# v1_2_0.net
KiCad netlist of a schematic drawn in EAGLE
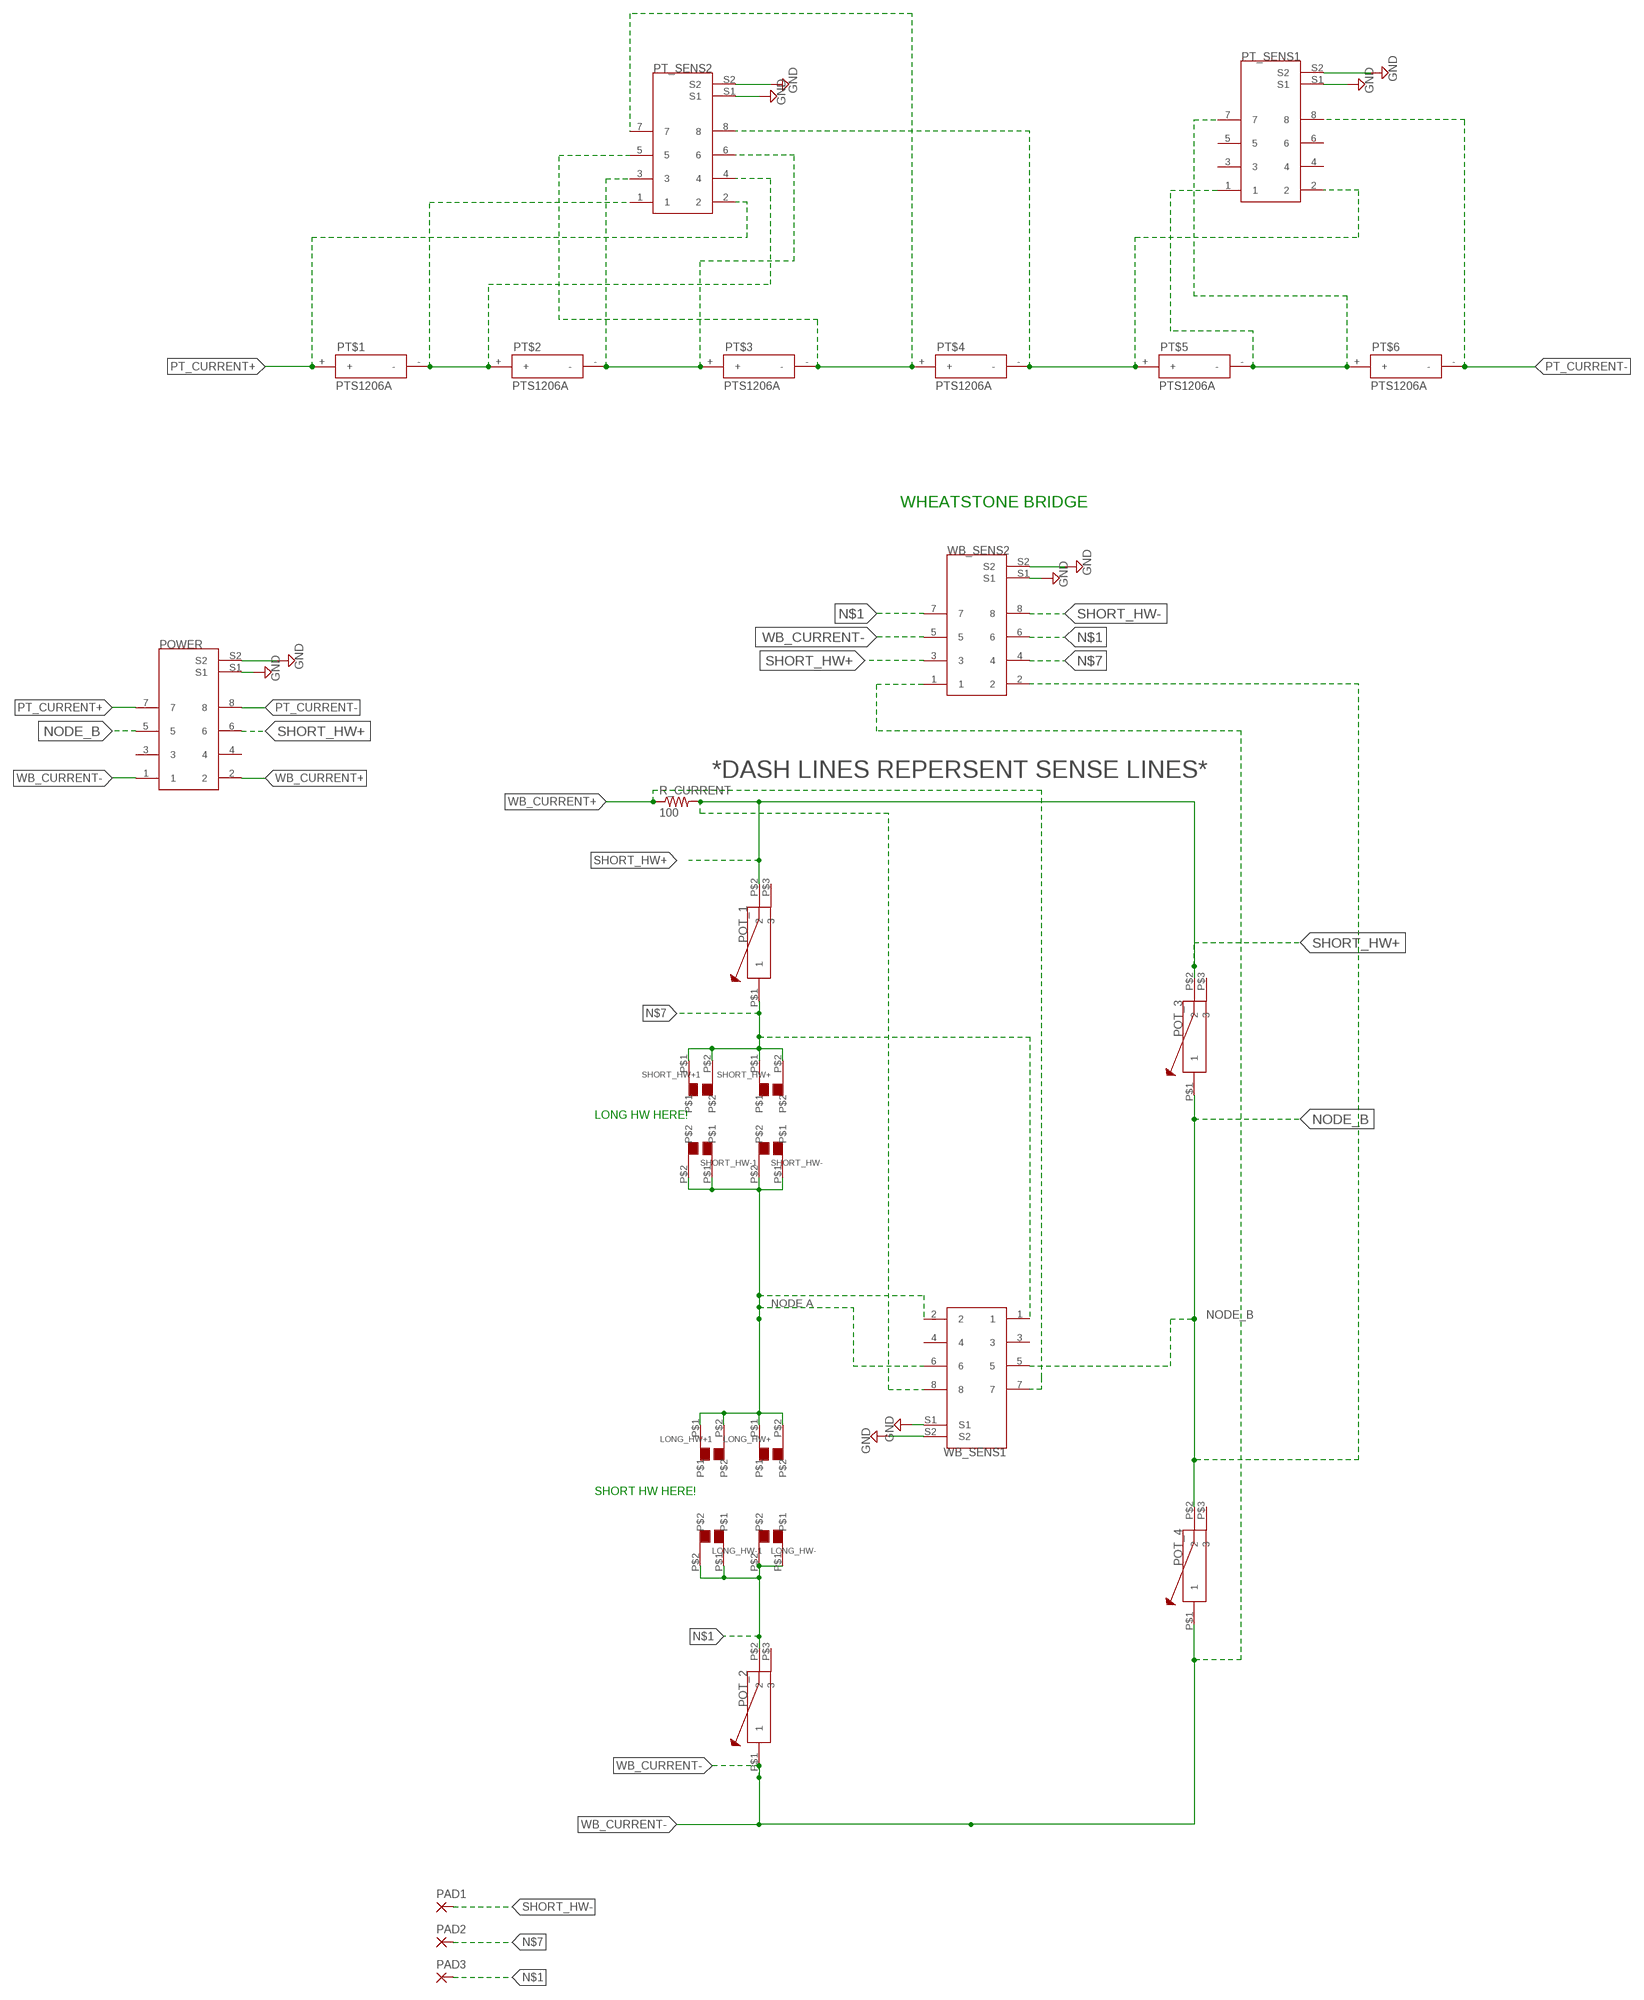
[diagram p0: schematic, sheet 1]

(export (version "E")
  (design (tool "Eeschema 10.0.6"))
  (components
    (comp (ref "LONG_HW+")
      (value "WIREPOINT_1A")
      (footprint "eagle-import:WIREPOINT")
      (libsource (lib "eagle-import") (part "WIREPOINT_1A"))
    )
    (comp (ref "LONG_HW+1")
      (value "WIREPOINT_1A")
      (footprint "eagle-import:WIREPOINT")
      (libsource (lib "eagle-import") (part "WIREPOINT_1A"))
    )
    (comp (ref "LONG_HW-")
      (value "WIREPOINT_1A")
      (footprint "eagle-import:WIREPOINT")
      (libsource (lib "eagle-import") (part "WIREPOINT_1A"))
    )
    (comp (ref "LONG_HW-1")
      (value "WIREPOINT_1A")
      (footprint "eagle-import:WIREPOINT")
      (libsource (lib "eagle-import") (part "WIREPOINT_1A"))
    )
    (comp (ref "PAD1")
      (value "2,15/1,0")
      (footprint "eagle-import:2,15_1,0")
      (libsource (lib "eagle-import") (part "2,15/1,0"))
    )
    (comp (ref "PAD2")
      (value "2,15/1,0")
      (footprint "eagle-import:2,15_1,0")
      (libsource (lib "eagle-import") (part "2,15/1,0"))
    )
    (comp (ref "PAD3")
      (value "2,15/1,0")
      (footprint "eagle-import:2,15_1,0")
      (libsource (lib "eagle-import") (part "2,15/1,0"))
    )
    (comp (ref "POT_1")
      (value "67WR200LFR$1")
      (footprint "eagle-import:67WR200LF")
      (libsource (lib "eagle-import") (part "67WR200LFR$1"))
    )
    (comp (ref "POT_2")
      (value "67WR200LFR$1")
      (footprint "eagle-import:67WR200LF")
      (libsource (lib "eagle-import") (part "67WR200LFR$1"))
    )
    (comp (ref "POT_3")
      (value "67WR200LFR$1")
      (footprint "eagle-import:67WR200LF")
      (libsource (lib "eagle-import") (part "67WR200LFR$1"))
    )
    (comp (ref "POT_4")
      (value "67WR200LFR$1")
      (footprint "eagle-import:67WR200LF")
      (libsource (lib "eagle-import") (part "67WR200LFR$1"))
    )
    (comp (ref "POWER")
      (value "RJ45_CONNECTOR")
      (footprint "eagle-import:RJ45_CONNNECTOR")
      (libsource (lib "eagle-import") (part "RJ45_CONNECTOR"))
    )
    (comp (ref "PT$1")
      (value "PTS1206A")
      (footprint "eagle-import:CAPMP3216X166")
      (libsource (lib "eagle-import") (part "PTS1206A"))
    )
    (comp (ref "PT$2")
      (value "PTS1206A")
      (footprint "eagle-import:CAPMP3216X166")
      (libsource (lib "eagle-import") (part "PTS1206A"))
    )
    (comp (ref "PT$3")
      (value "PTS1206A")
      (footprint "eagle-import:CAPMP3216X166")
      (libsource (lib "eagle-import") (part "PTS1206A"))
    )
    (comp (ref "PT$4")
      (value "PTS1206A")
      (footprint "eagle-import:CAPMP3216X166")
      (libsource (lib "eagle-import") (part "PTS1206A"))
    )
    (comp (ref "PT$5")
      (value "PTS1206A")
      (footprint "eagle-import:CAPMP3216X166")
      (libsource (lib "eagle-import") (part "PTS1206A"))
    )
    (comp (ref "PT$6")
      (value "PTS1206A")
      (footprint "eagle-import:CAPMP3216X166")
      (libsource (lib "eagle-import") (part "PTS1206A"))
    )
    (comp (ref "PT_SENS1")
      (value "RJ45_CONNECTOR")
      (footprint "eagle-import:RJ45_CONNNECTOR")
      (libsource (lib "eagle-import") (part "RJ45_CONNECTOR"))
    )
    (comp (ref "PT_SENS2")
      (value "RJ45_CONNECTOR")
      (footprint "eagle-import:RJ45_CONNNECTOR")
      (libsource (lib "eagle-import") (part "RJ45_CONNECTOR"))
    )
    (comp (ref "R_CURRENT")
      (value "100")
      (footprint "eagle-import:M0805")
      (libsource (lib "eagle-import") (part "R-US_M0805"))
    )
    (comp (ref "SHORT_HW+")
      (value "WIREPOINT_1A")
      (footprint "eagle-import:WIREPOINT")
      (libsource (lib "eagle-import") (part "WIREPOINT_1A"))
    )
    (comp (ref "SHORT_HW+1")
      (value "WIREPOINT_1A")
      (footprint "eagle-import:WIREPOINT")
      (libsource (lib "eagle-import") (part "WIREPOINT_1A"))
    )
    (comp (ref "SHORT_HW-")
      (value "WIREPOINT_1A")
      (footprint "eagle-import:WIREPOINT")
      (libsource (lib "eagle-import") (part "WIREPOINT_1A"))
    )
    (comp (ref "SHORT_HW-1")
      (value "WIREPOINT_1A")
      (footprint "eagle-import:WIREPOINT")
      (libsource (lib "eagle-import") (part "WIREPOINT_1A"))
    )
    (comp (ref "WB_SENS1")
      (value "RJ45_CONNECTOR")
      (footprint "eagle-import:RJ45_CONNNECTOR")
      (libsource (lib "eagle-import") (part "RJ45_CONNECTOR"))
    )
    (comp (ref "WB_SENS2")
      (value "RJ45_CONNECTOR")
      (footprint "eagle-import:RJ45_CONNNECTOR")
      (libsource (lib "eagle-import") (part "RJ45_CONNECTOR"))
    )
  )
  (nets
    (net (code "1") (name "GND") (class "Default")
      (node (ref "POWER") (pin "S1") (pinfunction "S1_S1") (pintype "bidirectional"))
      (node (ref "POWER") (pin "S2") (pinfunction "S2_S2") (pintype "bidirectional"))
      (node (ref "PT_SENS1") (pin "S1") (pinfunction "S1_S1") (pintype "bidirectional"))
      (node (ref "PT_SENS1") (pin "S2") (pinfunction "S2_S2") (pintype "bidirectional"))
      (node (ref "PT_SENS2") (pin "S1") (pinfunction "S1_S1") (pintype "bidirectional"))
      (node (ref "PT_SENS2") (pin "S2") (pinfunction "S2_S2") (pintype "bidirectional"))
      (node (ref "WB_SENS1") (pin "S1") (pinfunction "S1_S1") (pintype "bidirectional"))
      (node (ref "WB_SENS1") (pin "S2") (pinfunction "S2_S2") (pintype "bidirectional"))
      (node (ref "WB_SENS2") (pin "S1") (pinfunction "S1_S1") (pintype "bidirectional"))
      (node (ref "WB_SENS2") (pin "S2") (pinfunction "S2_S2") (pintype "bidirectional"))
    )
    (net (code "2") (name "N$1") (class "Default")
      (node (ref "LONG_HW-") (pin "P$1") (pinfunction "P$1_P$1") (pintype "bidirectional"))
      (node (ref "LONG_HW-") (pin "P$2") (pinfunction "P$2_P$2") (pintype "bidirectional"))
      (node (ref "LONG_HW-1") (pin "P$1") (pinfunction "P$1_P$1") (pintype "bidirectional"))
      (node (ref "LONG_HW-1") (pin "P$2") (pinfunction "P$2_P$2") (pintype "bidirectional"))
      (node (ref "PAD3") (pin "1") (pinfunction "P_1") (pintype "passive"))
      (node (ref "POT_2") (pin "P$2") (pinfunction "2_P$2") (pintype "bidirectional"))
      (node (ref "WB_SENS2") (pin "6") (pinfunction "6_6") (pintype "bidirectional"))
      (node (ref "WB_SENS2") (pin "7") (pinfunction "7_7") (pintype "bidirectional"))
    )
    (net (code "3") (name "N$7") (class "Default")
      (node (ref "PAD2") (pin "1") (pinfunction "P_1") (pintype "passive"))
      (node (ref "POT_1") (pin "P$1") (pinfunction "1_P$1") (pintype "bidirectional"))
      (node (ref "SHORT_HW+") (pin "P$1") (pinfunction "P$1_P$1") (pintype "bidirectional"))
      (node (ref "SHORT_HW+") (pin "P$2") (pinfunction "P$2_P$2") (pintype "bidirectional"))
      (node (ref "SHORT_HW+1") (pin "P$1") (pinfunction "P$1_P$1") (pintype "bidirectional"))
      (node (ref "SHORT_HW+1") (pin "P$2") (pinfunction "P$2_P$2") (pintype "bidirectional"))
      (node (ref "WB_SENS1") (pin "1") (pinfunction "1_1") (pintype "bidirectional"))
      (node (ref "WB_SENS2") (pin "4") (pinfunction "4_4") (pintype "bidirectional"))
    )
    (net (code "4") (name "NODE_B") (class "Default")
      (node (ref "POT_3") (pin "P$1") (pinfunction "1_P$1") (pintype "bidirectional"))
      (node (ref "POT_4") (pin "P$2") (pinfunction "2_P$2") (pintype "bidirectional"))
      (node (ref "POWER") (pin "5") (pinfunction "5_5") (pintype "bidirectional"))
      (node (ref "WB_SENS1") (pin "5") (pinfunction "5_5") (pintype "bidirectional"))
      (node (ref "WB_SENS2") (pin "2") (pinfunction "2_2") (pintype "bidirectional"))
    )
    (net (code "5") (name "Net-(PT$1-Pad-)") (class "Default")
      (node (ref "PT$1") (pin "-") (pinfunction "-_-") (pintype "bidirectional"))
      (node (ref "PT$2") (pin "+") (pinfunction "+_+") (pintype "bidirectional"))
      (node (ref "PT_SENS2") (pin "1") (pinfunction "1_1") (pintype "bidirectional"))
      (node (ref "PT_SENS2") (pin "4") (pinfunction "4_4") (pintype "bidirectional"))
    )
    (net (code "6") (name "Net-(PT$2-Pad-)") (class "Default")
      (node (ref "PT$2") (pin "-") (pinfunction "-_-") (pintype "bidirectional"))
      (node (ref "PT$3") (pin "+") (pinfunction "+_+") (pintype "bidirectional"))
      (node (ref "PT_SENS2") (pin "3") (pinfunction "3_3") (pintype "bidirectional"))
      (node (ref "PT_SENS2") (pin "6") (pinfunction "6_6") (pintype "bidirectional"))
    )
    (net (code "7") (name "Net-(PT$3-Pad-)") (class "Default")
      (node (ref "PT$3") (pin "-") (pinfunction "-_-") (pintype "bidirectional"))
      (node (ref "PT$4") (pin "+") (pinfunction "+_+") (pintype "bidirectional"))
      (node (ref "PT_SENS2") (pin "5") (pinfunction "5_5") (pintype "bidirectional"))
      (node (ref "PT_SENS2") (pin "7") (pinfunction "7_7") (pintype "bidirectional"))
    )
    (net (code "8") (name "Net-(PT$4-Pad-)") (class "Default")
      (node (ref "PT$4") (pin "-") (pinfunction "-_-") (pintype "bidirectional"))
      (node (ref "PT$5") (pin "+") (pinfunction "+_+") (pintype "bidirectional"))
      (node (ref "PT_SENS1") (pin "2") (pinfunction "2_2") (pintype "bidirectional"))
      (node (ref "PT_SENS2") (pin "8") (pinfunction "8_8") (pintype "bidirectional"))
    )
    (net (code "9") (name "Net-(PT$5-Pad-)") (class "Default")
      (node (ref "PT$5") (pin "-") (pinfunction "-_-") (pintype "bidirectional"))
      (node (ref "PT$6") (pin "+") (pinfunction "+_+") (pintype "bidirectional"))
      (node (ref "PT_SENS1") (pin "1") (pinfunction "1_1") (pintype "bidirectional"))
      (node (ref "PT_SENS1") (pin "7") (pinfunction "7_7") (pintype "bidirectional"))
    )
    (net (code "10") (name "PT_CURRENT+") (class "Default")
      (node (ref "POWER") (pin "7") (pinfunction "7_7") (pintype "bidirectional"))
      (node (ref "PT$1") (pin "+") (pinfunction "+_+") (pintype "bidirectional"))
      (node (ref "PT_SENS2") (pin "2") (pinfunction "2_2") (pintype "bidirectional"))
    )
    (net (code "11") (name "PT_CURRENT-") (class "Default")
      (node (ref "POWER") (pin "8") (pinfunction "8_8") (pintype "bidirectional"))
      (node (ref "PT$6") (pin "-") (pinfunction "-_-") (pintype "bidirectional"))
      (node (ref "PT_SENS1") (pin "8") (pinfunction "8_8") (pintype "bidirectional"))
    )
    (net (code "12") (name "SHORT_HW+") (class "Default")
      (node (ref "POT_1") (pin "P$2") (pinfunction "2_P$2") (pintype "bidirectional"))
      (node (ref "POT_3") (pin "P$2") (pinfunction "2_P$2") (pintype "bidirectional"))
      (node (ref "POWER") (pin "6") (pinfunction "6_6") (pintype "bidirectional"))
      (node (ref "R_CURRENT") (pin "2") (pinfunction "2_2") (pintype "passive"))
      (node (ref "WB_SENS1") (pin "8") (pinfunction "8_8") (pintype "bidirectional"))
      (node (ref "WB_SENS2") (pin "3") (pinfunction "3_3") (pintype "bidirectional"))
    )
    (net (code "13") (name "SHORT_HW-") (class "Default")
      (node (ref "LONG_HW+") (pin "P$1") (pinfunction "P$1_P$1") (pintype "bidirectional"))
      (node (ref "LONG_HW+") (pin "P$2") (pinfunction "P$2_P$2") (pintype "bidirectional"))
      (node (ref "LONG_HW+1") (pin "P$1") (pinfunction "P$1_P$1") (pintype "bidirectional"))
      (node (ref "LONG_HW+1") (pin "P$2") (pinfunction "P$2_P$2") (pintype "bidirectional"))
      (node (ref "PAD1") (pin "1") (pinfunction "P_1") (pintype "passive"))
      (node (ref "SHORT_HW-") (pin "P$1") (pinfunction "P$1_P$1") (pintype "bidirectional"))
      (node (ref "SHORT_HW-") (pin "P$2") (pinfunction "P$2_P$2") (pintype "bidirectional"))
      (node (ref "SHORT_HW-1") (pin "P$1") (pinfunction "P$1_P$1") (pintype "bidirectional"))
      (node (ref "SHORT_HW-1") (pin "P$2") (pinfunction "P$2_P$2") (pintype "bidirectional"))
      (node (ref "WB_SENS1") (pin "2") (pinfunction "2_2") (pintype "bidirectional"))
      (node (ref "WB_SENS1") (pin "6") (pinfunction "6_6") (pintype "bidirectional"))
      (node (ref "WB_SENS2") (pin "8") (pinfunction "8_8") (pintype "bidirectional"))
    )
    (net (code "14") (name "WB_CURRENT+") (class "Default")
      (node (ref "POWER") (pin "2") (pinfunction "2_2") (pintype "bidirectional"))
      (node (ref "R_CURRENT") (pin "1") (pinfunction "1_1") (pintype "passive"))
      (node (ref "WB_SENS1") (pin "7") (pinfunction "7_7") (pintype "bidirectional"))
    )
    (net (code "15") (name "WB_CURRENT-") (class "Default")
      (node (ref "POT_2") (pin "P$1") (pinfunction "1_P$1") (pintype "bidirectional"))
      (node (ref "POT_4") (pin "P$1") (pinfunction "1_P$1") (pintype "bidirectional"))
      (node (ref "POWER") (pin "1") (pinfunction "1_1") (pintype "bidirectional"))
      (node (ref "WB_SENS2") (pin "1") (pinfunction "1_1") (pintype "bidirectional"))
      (node (ref "WB_SENS2") (pin "5") (pinfunction "5_5") (pintype "bidirectional"))
    )
    (net (code "16") (name "unconnected-(POT_1-3-PadP$3)") (class "Default")
      (node (ref "POT_1") (pin "P$3") (pinfunction "3_P$3") (pintype "bidirectional"))
    )
    (net (code "17") (name "unconnected-(POT_2-3-PadP$3)") (class "Default")
      (node (ref "POT_2") (pin "P$3") (pinfunction "3_P$3") (pintype "bidirectional"))
    )
    (net (code "18") (name "unconnected-(POT_3-3-PadP$3)") (class "Default")
      (node (ref "POT_3") (pin "P$3") (pinfunction "3_P$3") (pintype "bidirectional"))
    )
    (net (code "19") (name "unconnected-(POT_4-3-PadP$3)") (class "Default")
      (node (ref "POT_4") (pin "P$3") (pinfunction "3_P$3") (pintype "bidirectional"))
    )
    (net (code "20") (name "unconnected-(POWER-Pad3)") (class "Default")
      (node (ref "POWER") (pin "3") (pinfunction "3_3") (pintype "bidirectional"))
    )
    (net (code "21") (name "unconnected-(POWER-Pad4)") (class "Default")
      (node (ref "POWER") (pin "4") (pinfunction "4_4") (pintype "bidirectional"))
    )
    (net (code "22") (name "unconnected-(PT_SENS1-Pad3)") (class "Default")
      (node (ref "PT_SENS1") (pin "3") (pinfunction "3_3") (pintype "bidirectional"))
    )
    (net (code "23") (name "unconnected-(PT_SENS1-Pad4)") (class "Default")
      (node (ref "PT_SENS1") (pin "4") (pinfunction "4_4") (pintype "bidirectional"))
    )
    (net (code "24") (name "unconnected-(PT_SENS1-Pad5)") (class "Default")
      (node (ref "PT_SENS1") (pin "5") (pinfunction "5_5") (pintype "bidirectional"))
    )
    (net (code "25") (name "unconnected-(PT_SENS1-Pad6)") (class "Default")
      (node (ref "PT_SENS1") (pin "6") (pinfunction "6_6") (pintype "bidirectional"))
    )
    (net (code "26") (name "unconnected-(WB_SENS1-Pad3)") (class "Default")
      (node (ref "WB_SENS1") (pin "3") (pinfunction "3_3") (pintype "bidirectional"))
    )
    (net (code "27") (name "unconnected-(WB_SENS1-Pad4)") (class "Default")
      (node (ref "WB_SENS1") (pin "4") (pinfunction "4_4") (pintype "bidirectional"))
    )
  )
)
